# nm_main.net
KiCad netlist of a schematic drawn in Altium Designer
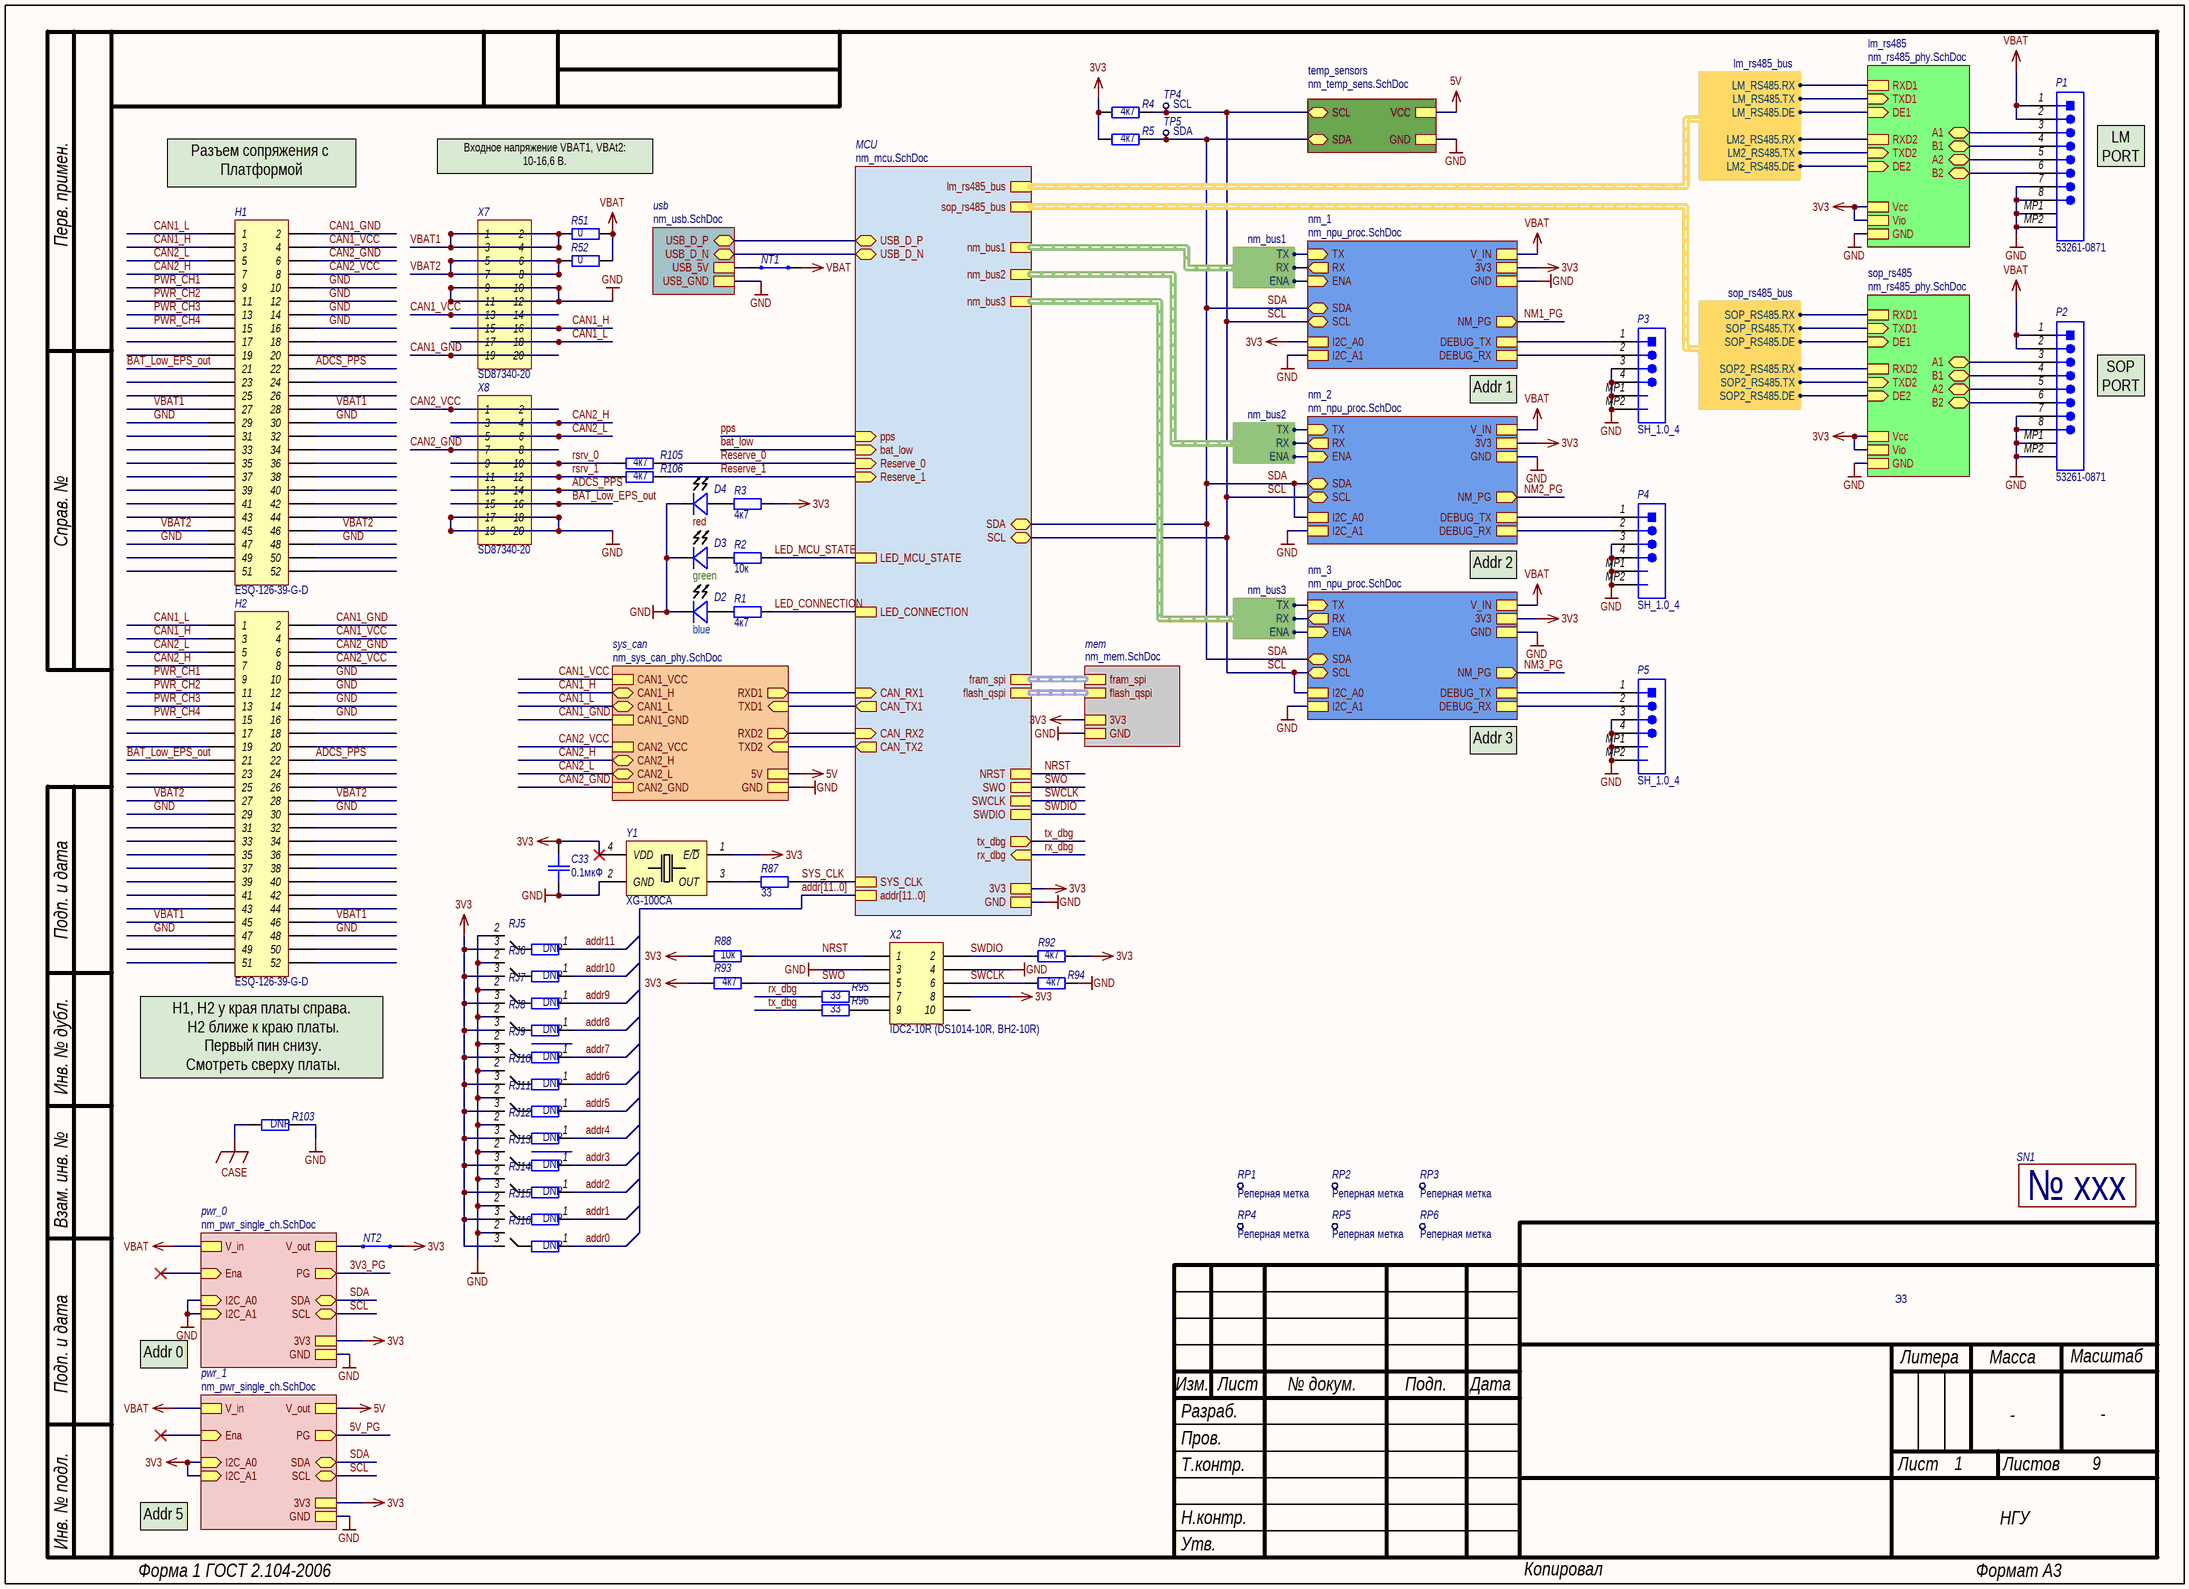
[diagram p0: nm_main.SchDoc]

(export (version "E")
  (design (tool "Eeschema 10.0.6"))
  (components
    (comp (ref "C33")
      (value "0.1мкФ")
      (footprint "SMD_C0603")
      (description "Capacitor")
      (libsource (lib "Passive") (part "Capacitor"))
    )
    (comp (ref "D2")
      (value "blue")
      (footprint "LED_0603")
      (fields (field (name "Comment") "LED"))
      (libsource (lib "LED") (part "LED"))
    )
    (comp (ref "D3")
      (value "green")
      (footprint "LED_0603")
      (fields (field (name "Comment") "LED"))
      (libsource (lib "LED") (part "LED"))
    )
    (comp (ref "D4")
      (value "red")
      (footprint "LED_0603")
      (fields (field (name "Comment") "LED"))
      (libsource (lib "LED") (part "LED"))
    )
    (comp (ref "H1")
      (value "ESQ-126-39-G-D")
      (footprint "ESQ-126-39-G-D")
      (description "Elevated socket, dual-row, 26-pin per row")
      (fields (field (name "НАИМЕНОВАНИЕ") "ESQ-126-39-G-D"))
      (libsource (lib "Connector") (part "ESQ-126-39-G-D"))
    )
    (comp (ref "H2")
      (value "ESQ-126-39-G-D")
      (footprint "ESQ-126-39-G-D")
      (description "Elevated socket, dual-row, 26-pin per row")
      (fields (field (name "НАИМЕНОВАНИЕ") "ESQ-126-39-G-D"))
      (libsource (lib "Connector") (part "ESQ-126-39-G-D"))
    )
    (comp (ref "NT1")
      (value "OSM R1-8")
      (footprint "NetTie_1mm")
      (description "Different Nets connection")
      (libsource (lib "Passive") (part "NetTie"))
    )
    (comp (ref "NT2")
      (value "OSM R1-8")
      (footprint "NetTie_1mm")
      (description "Different Nets connection")
      (libsource (lib "Passive") (part "NetTie"))
    )
    (comp (ref "P1")
      (value "53261-0871")
      (footprint "53261-0871")
      (description "Male Header, Pitch 1.25 mm, 1 x 8 Position, Height 3.4 mm, -40 to 85 degC, RoHS, Tape and Reel")
      (fields (field (name "НАИМЕНОВАНИЕ") "53261-0871"))
      (libsource (lib "Connector") (part "PicoBlade_53261-0871"))
    )
    (comp (ref "P2")
      (value "53261-0871")
      (footprint "53261-0871")
      (description "Male Header, Pitch 1.25 mm, 1 x 8 Position, Height 3.4 mm, -40 to 85 degC, RoHS, Tape and Reel")
      (fields (field (name "НАИМЕНОВАНИЕ") "53261-0871"))
      (libsource (lib "Connector") (part "PicoBlade_53261-0871"))
    )
    (comp (ref "P3")
      (value "SH_1.0_4")
      (footprint "53261-0471")
      (description "JST SH1.0, 1.0 mm pitch/Disconnactable crimp style connectors")
      (fields (field (name "НАИМЕНОВАНИЕ") "SH_1.0_4"))
      (libsource (lib "Connector") (part "SH_1.0_4"))
    )
    (comp (ref "P4")
      (value "SH_1.0_4")
      (footprint "53261-0471")
      (description "JST SH1.0, 1.0 mm pitch/Disconnactable crimp style connectors")
      (fields (field (name "НАИМЕНОВАНИЕ") "SH_1.0_4"))
      (libsource (lib "Connector") (part "SH_1.0_4"))
    )
    (comp (ref "P5")
      (value "SH_1.0_4")
      (footprint "53261-0471")
      (description "JST SH1.0, 1.0 mm pitch/Disconnactable crimp style connectors")
      (fields (field (name "НАИМЕНОВАНИЕ") "SH_1.0_4"))
      (libsource (lib "Connector") (part "SH_1.0_4"))
    )
    (comp (ref "R1")
      (value "4к7")
      (footprint "SMD_0603")
      (description "Resistor")
      (libsource (lib "") (part "Resistor_2"))
    )
    (comp (ref "R2")
      (value "10к")
      (footprint "SMD_0603")
      (description "Resistor")
      (libsource (lib "") (part "Resistor_2"))
    )
    (comp (ref "R3")
      (value "4к7")
      (footprint "SMD_0603")
      (description "Resistor")
      (libsource (lib "") (part "Resistor_2"))
    )
    (comp (ref "R4")
      (value "4к7")
      (footprint "SMD_0603")
      (description "Resistor")
      (libsource (lib "Passive") (part "Resistor"))
    )
    (comp (ref "R5")
      (value "4к7")
      (footprint "SMD_0603")
      (description "Resistor")
      (libsource (lib "Passive") (part "Resistor"))
    )
    (comp (ref "R51")
      (value "0")
      (footprint "SMD_1206")
      (description "Resistor")
      (libsource (lib "") (part "Resistor_3"))
    )
    (comp (ref "R52")
      (value "0")
      (footprint "SMD_1206")
      (description "Resistor")
      (libsource (lib "") (part "Resistor_3"))
    )
    (comp (ref "R87")
      (value "33")
      (footprint "SMD_0603")
      (description "Resistor")
      (libsource (lib "") (part "Resistor_1"))
    )
    (comp (ref "R88")
      (value "10к")
      (footprint "SMD_0603")
      (description "Resistor")
      (libsource (lib "") (part "Resistor_3"))
    )
    (comp (ref "R92")
      (value "4к7")
      (footprint "SMD_0603")
      (description "Resistor")
      (libsource (lib "") (part "Resistor_1"))
    )
    (comp (ref "R93")
      (value "4к7")
      (footprint "SMD_0603")
      (description "Resistor")
      (libsource (lib "Passive") (part "Resistor"))
    )
    (comp (ref "R94")
      (value "4к7")
      (footprint "SMD_0603")
      (description "Resistor")
      (libsource (lib "Passive") (part "Resistor"))
    )
    (comp (ref "R95")
      (value "33")
      (footprint "SMD_0603")
      (description "Resistor")
      (libsource (lib "") (part "Resistor_1"))
    )
    (comp (ref "R96")
      (value "33")
      (footprint "SMD_0603")
      (description "Resistor")
      (libsource (lib "") (part "Resistor_1"))
    )
    (comp (ref "R103")
      (value "DNP")
      (footprint "SMD_0805")
      (description "Resistor")
      (libsource (lib "Passive") (part "Resistor"))
    )
    (comp (ref "R105")
      (value "4к7")
      (footprint "SMD_0603")
      (description "Resistor")
      (libsource (lib "") (part "Resistor_2"))
    )
    (comp (ref "R106")
      (value "4к7")
      (footprint "SMD_0603")
      (description "Resistor")
      (libsource (lib "") (part "Resistor_2"))
    )
    (comp (ref "RJ5")
      (value "DNP")
      (footprint "SMD_JMP_0402")
      (description "Resistor-Jumper")
      (fields (field (name "Comment") "OSM R1-8"))
      (libsource (lib "Passive") (part "Resistor_Jamper"))
    )
    (comp (ref "RJ6")
      (value "DNP")
      (footprint "SMD_JMP_0402")
      (description "Resistor-Jumper")
      (fields (field (name "Comment") "OSM R1-8"))
      (libsource (lib "Passive") (part "Resistor_Jamper"))
    )
    (comp (ref "RJ7")
      (value "DNP")
      (footprint "SMD_JMP_0402")
      (description "Resistor-Jumper")
      (fields (field (name "Comment") "OSM R1-8"))
      (libsource (lib "Passive") (part "Resistor_Jamper"))
    )
    (comp (ref "RJ8")
      (value "DNP")
      (footprint "SMD_JMP_0402")
      (description "Resistor-Jumper")
      (fields (field (name "Comment") "OSM R1-8"))
      (libsource (lib "Passive") (part "Resistor_Jamper"))
    )
    (comp (ref "RJ9")
      (value "DNP")
      (footprint "SMD_JMP_0402")
      (description "Resistor-Jumper")
      (fields (field (name "Comment") "OSM R1-8"))
      (libsource (lib "Passive") (part "Resistor_Jamper"))
    )
    (comp (ref "RJ10")
      (value "DNP")
      (footprint "SMD_JMP_0402")
      (description "Resistor-Jumper")
      (fields (field (name "Comment") "OSM R1-8"))
      (libsource (lib "Passive") (part "Resistor_Jamper"))
    )
    (comp (ref "RJ11")
      (value "DNP")
      (footprint "SMD_JMP_0402")
      (description "Resistor-Jumper")
      (fields (field (name "Comment") "OSM R1-8"))
      (libsource (lib "Passive") (part "Resistor_Jamper"))
    )
    (comp (ref "RJ12")
      (value "DNP")
      (footprint "SMD_JMP_0402")
      (description "Resistor-Jumper")
      (fields (field (name "Comment") "OSM R1-8"))
      (libsource (lib "Passive") (part "Resistor_Jamper"))
    )
    (comp (ref "RJ13")
      (value "DNP")
      (footprint "SMD_JMP_0402")
      (description "Resistor-Jumper")
      (fields (field (name "Comment") "OSM R1-8"))
      (libsource (lib "Passive") (part "Resistor_Jamper"))
    )
    (comp (ref "RJ14")
      (value "DNP")
      (footprint "SMD_JMP_0402")
      (description "Resistor-Jumper")
      (fields (field (name "Comment") "OSM R1-8"))
      (libsource (lib "Passive") (part "Resistor_Jamper"))
    )
    (comp (ref "RJ15")
      (value "DNP")
      (footprint "SMD_JMP_0402")
      (description "Resistor-Jumper")
      (fields (field (name "Comment") "OSM R1-8"))
      (libsource (lib "Passive") (part "Resistor_Jamper"))
    )
    (comp (ref "RJ16")
      (value "DNP")
      (footprint "SMD_JMP_0402")
      (description "Resistor-Jumper")
      (fields (field (name "Comment") "OSM R1-8"))
      (libsource (lib "Passive") (part "Resistor_Jamper"))
    )
    (comp (ref "RP1")
      (value "RP")
      (footprint "ReperPoint")
      (fields (field (name "НАИМЕНОВАНИЕ") "Реперная метка"))
      (libsource (lib "Connector") (part "RP"))
    )
    (comp (ref "RP2")
      (value "RP")
      (footprint "ReperPoint")
      (fields (field (name "НАИМЕНОВАНИЕ") "Реперная метка"))
      (libsource (lib "Connector") (part "RP"))
    )
    (comp (ref "RP3")
      (value "RP")
      (footprint "ReperPoint")
      (fields (field (name "НАИМЕНОВАНИЕ") "Реперная метка"))
      (libsource (lib "Connector") (part "RP"))
    )
    (comp (ref "RP4")
      (value "RP")
      (footprint "ReperPoint")
      (fields (field (name "НАИМЕНОВАНИЕ") "Реперная метка"))
      (libsource (lib "Connector") (part "RP"))
    )
    (comp (ref "RP5")
      (value "RP")
      (footprint "ReperPoint")
      (fields (field (name "НАИМЕНОВАНИЕ") "Реперная метка"))
      (libsource (lib "Connector") (part "RP"))
    )
    (comp (ref "RP6")
      (value "RP")
      (footprint "ReperPoint")
      (fields (field (name "НАИМЕНОВАНИЕ") "Реперная метка"))
      (libsource (lib "Connector") (part "RP"))
    )
    (comp (ref "SN1")
      (value "Место под нанесение серийного номера")
      (footprint "Serial_number_v2")
      (libsource (lib "Serial_number") (part "Serial_number"))
    )
    (comp (ref "TP4")
      (value "SCL")
      (footprint "TP_PAD_1")
      (fields (field (name "TP_NAME") "SCL"))
      (libsource (lib "Connector") (part "TP"))
    )
    (comp (ref "TP5")
      (value "SDA")
      (footprint "TP_PAD_1")
      (fields (field (name "TP_NAME") "SDA"))
      (libsource (lib "Connector") (part "TP"))
    )
    (comp (ref "X2")
      (value "Header 2X10")
      (footprint "IDC2-10R")
      (description "Header, 10-Pin, Dual row")
      (fields (field (name "НАИМЕНОВАНИЕ") "IDC2-10R (DS1014-10R, BH2-10R)"))
      (libsource (lib "Header 2X10") (part "Header 2X10"))
    )
    (comp (ref "X7")
      (value "Header 2X20")
      (footprint "PLD2-20_SD87340-20")
      (description "Header, 20-Pin, Dual row")
      (fields (field (name "НАИМЕНОВАНИЕ") "SD87340-20"))
      (libsource (lib "Connector") (part "Header 2X20"))
    )
    (comp (ref "X8")
      (value "Header 2X20")
      (footprint "PLD2-20_SD87340-20")
      (description "Header, 20-Pin, Dual row")
      (fields (field (name "НАИМЕНОВАНИЕ") "SD87340-20"))
      (libsource (lib "Connector") (part "Header 2X20"))
    )
    (comp (ref "Y1")
      (value "XG-1000CA")
      (footprint "SMD_7050_Crystal_Oscillator")
      (description "Crystall oscillator, CMOS, 3.3V, SMD7050")
      (fields (field (name "НАИМЕНОВАНИЕ") "XG-100CA"))
      (libsource (lib "Oscillator") (part "Crystal_Oscillator"))
    )
  )
  (nets
    (net (code "8") (name "/A1") (class "Default")
      (node (ref "P1") (pin "3") (pinfunction "3_3") (pintype "passive"))
    )
    (net (code "9") (name "/A1_1") (class "Default")
      (node (ref "P2") (pin "3") (pinfunction "3_3") (pintype "passive"))
    )
    (net (code "10") (name "/A2") (class "Default")
      (node (ref "P1") (pin "5") (pinfunction "5_5") (pintype "passive"))
    )
    (net (code "11") (name "/A2_1") (class "Default")
      (node (ref "P2") (pin "5") (pinfunction "5_5") (pintype "passive"))
    )
    (net (code "12") (name "/ADCS_PPS") (class "Default")
      (node (ref "H1") (pin "22") (pinfunction "22_22") (pintype "passive"))
      (node (ref "H2") (pin "22") (pinfunction "22_22") (pintype "passive"))
      (node (ref "X8") (pin "13") (pinfunction "13_13") (pintype "passive"))
      (node (ref "X8") (pin "14") (pinfunction "14_14") (pintype "passive"))
    )
    (net (code "13") (name "/B1") (class "Default")
      (node (ref "P1") (pin "4") (pinfunction "4_4") (pintype "passive"))
    )
    (net (code "14") (name "/B1_1") (class "Default")
      (node (ref "P2") (pin "4") (pinfunction "4_4") (pintype "passive"))
    )
    (net (code "15") (name "/B2") (class "Default")
      (node (ref "P1") (pin "6") (pinfunction "6_6") (pintype "passive"))
    )
    (net (code "16") (name "/B2_1") (class "Default")
      (node (ref "P2") (pin "6") (pinfunction "6_6") (pintype "passive"))
    )
    (net (code "17") (name "/BAT_Low_EPS_out") (class "Default")
      (node (ref "H1") (pin "21") (pinfunction "21_21") (pintype "passive"))
      (node (ref "H2") (pin "21") (pinfunction "21_21") (pintype "passive"))
      (node (ref "X8") (pin "15") (pinfunction "15_15") (pintype "passive"))
      (node (ref "X8") (pin "16") (pinfunction "16_16") (pintype "passive"))
    )
    (net (code "18") (name "/CAN1_GND") (class "Default")
      (node (ref "H1") (pin "2") (pinfunction "2_2") (pintype "passive"))
      (node (ref "H2") (pin "2") (pinfunction "2_2") (pintype "passive"))
      (node (ref "X7") (pin "19") (pinfunction "19_19") (pintype "passive"))
      (node (ref "X7") (pin "20") (pinfunction "20_20") (pintype "passive"))
    )
    (net (code "19") (name "/CAN1_H") (class "Default")
      (node (ref "H1") (pin "3") (pinfunction "3_3") (pintype "passive"))
      (node (ref "H2") (pin "3") (pinfunction "3_3") (pintype "passive"))
      (node (ref "X7") (pin "15") (pinfunction "15_15") (pintype "passive"))
      (node (ref "X7") (pin "16") (pinfunction "16_16") (pintype "passive"))
    )
    (net (code "20") (name "/CAN1_L") (class "Default")
      (node (ref "H1") (pin "1") (pinfunction "1_1") (pintype "passive"))
      (node (ref "H2") (pin "1") (pinfunction "1_1") (pintype "passive"))
      (node (ref "X7") (pin "17") (pinfunction "17_17") (pintype "passive"))
      (node (ref "X7") (pin "18") (pinfunction "18_18") (pintype "passive"))
    )
    (net (code "21") (name "/CAN1_VCC") (class "Default")
      (node (ref "H1") (pin "4") (pinfunction "4_4") (pintype "passive"))
      (node (ref "H2") (pin "4") (pinfunction "4_4") (pintype "passive"))
      (node (ref "X7") (pin "13") (pinfunction "13_13") (pintype "passive"))
      (node (ref "X7") (pin "14") (pinfunction "14_14") (pintype "passive"))
    )
    (net (code "22") (name "/CAN2_GND") (class "Default")
      (node (ref "H1") (pin "6") (pinfunction "6_6") (pintype "passive"))
      (node (ref "H2") (pin "6") (pinfunction "6_6") (pintype "passive"))
      (node (ref "X8") (pin "7") (pinfunction "7_7") (pintype "passive"))
      (node (ref "X8") (pin "8") (pinfunction "8_8") (pintype "passive"))
    )
    (net (code "23") (name "/CAN2_H") (class "Default")
      (node (ref "H1") (pin "7") (pinfunction "7_7") (pintype "passive"))
      (node (ref "H2") (pin "7") (pinfunction "7_7") (pintype "passive"))
      (node (ref "X8") (pin "3") (pinfunction "3_3") (pintype "passive"))
      (node (ref "X8") (pin "4") (pinfunction "4_4") (pintype "passive"))
    )
    (net (code "24") (name "/CAN2_L") (class "Default")
      (node (ref "H1") (pin "5") (pinfunction "5_5") (pintype "passive"))
      (node (ref "H2") (pin "5") (pinfunction "5_5") (pintype "passive"))
      (node (ref "X8") (pin "5") (pinfunction "5_5") (pintype "passive"))
      (node (ref "X8") (pin "6") (pinfunction "6_6") (pintype "passive"))
    )
    (net (code "25") (name "/CAN2_VCC") (class "Default")
      (node (ref "H1") (pin "8") (pinfunction "8_8") (pintype "passive"))
      (node (ref "H2") (pin "8") (pinfunction "8_8") (pintype "passive"))
      (node (ref "X8") (pin "1") (pinfunction "1_1") (pintype "passive"))
      (node (ref "X8") (pin "2") (pinfunction "2_2") (pintype "passive"))
    )
    (net (code "32") (name "/DEBUG_RX") (class "Default")
      (node (ref "P3") (pin "2") (pinfunction "2_2") (pintype "passive"))
    )
    (net (code "33") (name "/DEBUG_RX_1") (class "Default")
      (node (ref "P4") (pin "2") (pinfunction "2_2") (pintype "passive"))
    )
    (net (code "34") (name "/DEBUG_RX_2") (class "Default")
      (node (ref "P5") (pin "2") (pinfunction "2_2") (pintype "passive"))
    )
    (net (code "35") (name "/DEBUG_TX") (class "Default")
      (node (ref "P3") (pin "1") (pinfunction "1_1") (pintype "passive"))
    )
    (net (code "36") (name "/DEBUG_TX_1") (class "Default")
      (node (ref "P4") (pin "1") (pinfunction "1_1") (pintype "passive"))
    )
    (net (code "37") (name "/DEBUG_TX_2") (class "Default")
      (node (ref "P5") (pin "1") (pinfunction "1_1") (pintype "passive"))
    )
    (net (code "43") (name "/LED_CONNECTION") (class "Default")
      (node (ref "R1") (pin "1") (pinfunction "1_1") (pintype "passive"))
    )
    (net (code "44") (name "/LED_MCU_STATE") (class "Default")
      (node (ref "R2") (pin "1") (pinfunction "1_1") (pintype "passive"))
    )
    (net (code "48") (name "/NRST") (class "Default")
      (node (ref "R88") (pin "2") (pinfunction "2_2") (pintype "passive"))
      (node (ref "X2") (pin "1") (pinfunction "1_1") (pintype "passive"))
    )
    (net (code "49") (name "/PWR_CH1") (class "Default")
      (node (ref "H1") (pin "9") (pinfunction "9_9") (pintype "passive"))
      (node (ref "H2") (pin "9") (pinfunction "9_9") (pintype "passive"))
    )
    (net (code "50") (name "/PWR_CH2") (class "Default")
      (node (ref "H1") (pin "11") (pinfunction "11_11") (pintype "passive"))
      (node (ref "H2") (pin "11") (pinfunction "11_11") (pintype "passive"))
    )
    (net (code "51") (name "/PWR_CH3") (class "Default")
      (node (ref "H1") (pin "13") (pinfunction "13_13") (pintype "passive"))
      (node (ref "H2") (pin "13") (pinfunction "13_13") (pintype "passive"))
    )
    (net (code "52") (name "/PWR_CH4") (class "Default")
      (node (ref "H1") (pin "15") (pinfunction "15_15") (pintype "passive"))
      (node (ref "H2") (pin "15") (pinfunction "15_15") (pintype "passive"))
    )
    (net (code "62") (name "/Reserve_0") (class "Default")
      (node (ref "R105") (pin "1") (pinfunction "1_1") (pintype "passive"))
    )
    (net (code "63") (name "/Reserve_1") (class "Default")
      (node (ref "R106") (pin "1") (pinfunction "1_1") (pintype "passive"))
    )
    (net (code "64") (name "/SCL") (class "Default")
      (node (ref "R4") (pin "1") (pinfunction "1_1") (pintype "passive"))
      (node (ref "TP4") (pin "0") (pinfunction "TP_0") (pintype "passive"))
    )
    (net (code "65") (name "/SDA") (class "Default")
      (node (ref "R5") (pin "1") (pinfunction "1_1") (pintype "passive"))
      (node (ref "TP5") (pin "0") (pinfunction "TP_0") (pintype "passive"))
    )
    (net (code "66") (name "/SWCLK") (class "Default")
      (node (ref "R94") (pin "2") (pinfunction "2_2") (pintype "passive"))
      (node (ref "X2") (pin "6") (pinfunction "6_6") (pintype "passive"))
    )
    (net (code "67") (name "/SWDIO") (class "Default")
      (node (ref "R92") (pin "1") (pinfunction "1_1") (pintype "passive"))
      (node (ref "X2") (pin "2") (pinfunction "2_2") (pintype "passive"))
    )
    (net (code "68") (name "/SWO") (class "Default")
      (node (ref "R93") (pin "1") (pinfunction "1_1") (pintype "passive"))
      (node (ref "X2") (pin "5") (pinfunction "5_5") (pintype "passive"))
    )
    (net (code "69") (name "/SYS_CLK") (class "Default")
      (node (ref "R87") (pin "2") (pinfunction "2_2") (pintype "passive"))
    )
    (net (code "77") (name "/USB_5V") (class "Default")
      (node (ref "NT1") (pin "1") (pinfunction "1_1") (pintype "passive"))
    )
    (net (code "80") (name "/VBAT1") (class "Default")
      (node (ref "H1") (pin "27") (pinfunction "27_27") (pintype "passive"))
      (node (ref "H1") (pin "28") (pinfunction "28_28") (pintype "passive"))
      (node (ref "H2") (pin "45") (pinfunction "45_45") (pintype "passive"))
      (node (ref "H2") (pin "46") (pinfunction "46_46") (pintype "passive"))
      (node (ref "R51") (pin "1") (pinfunction "1_1") (pintype "passive"))
      (node (ref "X7") (pin "1") (pinfunction "1_1") (pintype "passive"))
      (node (ref "X7") (pin "2") (pinfunction "2_2") (pintype "passive"))
      (node (ref "X7") (pin "3") (pinfunction "3_3") (pintype "passive"))
      (node (ref "X7") (pin "4") (pinfunction "4_4") (pintype "passive"))
    )
    (net (code "81") (name "/VBAT2") (class "Default")
      (node (ref "H1") (pin "45") (pinfunction "45_45") (pintype "passive"))
      (node (ref "H1") (pin "46") (pinfunction "46_46") (pintype "passive"))
      (node (ref "H2") (pin "27") (pinfunction "27_27") (pintype "passive"))
      (node (ref "H2") (pin "28") (pinfunction "28_28") (pintype "passive"))
      (node (ref "R52") (pin "1") (pinfunction "1_1") (pintype "passive"))
      (node (ref "X7") (pin "5") (pinfunction "5_5") (pintype "passive"))
      (node (ref "X7") (pin "6") (pinfunction "6_6") (pintype "passive"))
      (node (ref "X7") (pin "7") (pinfunction "7_7") (pintype "passive"))
      (node (ref "X7") (pin "8") (pinfunction "8_8") (pintype "passive"))
    )
    (net (code "82") (name "/V_out") (class "Default")
      (node (ref "NT2") (pin "1") (pinfunction "1_1") (pintype "passive"))
    )
    (net (code "83") (name "/addr0") (class "Default") (node (ref "RJ16") (pin "1") (pintype "passive")))
    (net (code "84") (name "/addr1") (class "Default") (node (ref "RJ15") (pin "1") (pintype "passive")))
    (net (code "85") (name "/addr2") (class "Default") (node (ref "RJ14") (pin "1") (pintype "passive")))
    (net (code "86") (name "/addr3") (class "Default") (node (ref "RJ13") (pin "1") (pintype "passive")))
    (net (code "87") (name "/addr4") (class "Default") (node (ref "RJ12") (pin "1") (pintype "passive")))
    (net (code "88") (name "/addr5") (class "Default") (node (ref "RJ11") (pin "1") (pintype "passive")))
    (net (code "89") (name "/addr6") (class "Default") (node (ref "RJ10") (pin "1") (pintype "passive")))
    (net (code "90") (name "/addr7") (class "Default") (node (ref "RJ9") (pin "1") (pintype "passive")))
    (net (code "91") (name "/addr8") (class "Default") (node (ref "RJ8") (pin "1") (pintype "passive")))
    (net (code "92") (name "/addr9") (class "Default") (node (ref "RJ7") (pin "1") (pintype "passive")))
    (net (code "93") (name "/addr10") (class "Default") (node (ref "RJ6") (pin "1") (pintype "passive")))
    (net (code "94") (name "/addr11") (class "Default") (node (ref "RJ5") (pin "1") (pintype "passive")))
    (net (code "100") (name "/rsrv_0") (class "Default")
      (node (ref "R105") (pin "2") (pinfunction "2_2") (pintype "passive"))
      (node (ref "X8") (pin "10") (pinfunction "10_10") (pintype "passive"))
      (node (ref "X8") (pin "9") (pinfunction "9_9") (pintype "passive"))
    )
    (net (code "101") (name "/rsrv_1") (class "Default")
      (node (ref "R106") (pin "2") (pinfunction "2_2") (pintype "passive"))
      (node (ref "X8") (pin "11") (pinfunction "11_11") (pintype "passive"))
      (node (ref "X8") (pin "12") (pinfunction "12_12") (pintype "passive"))
    )
    (net (code "102") (name "/rx_dbg") (class "Default")
      (node (ref "R95") (pin "1") (pinfunction "1_1") (pintype "passive"))
    )
    (net (code "103") (name "/tx_dbg") (class "Default")
      (node (ref "R96") (pin "1") (pinfunction "1_1") (pintype "passive"))
    )
    (net (code "109") (name "3V3") (class "Default")
      (node (ref "C33") (pin "2") (pinfunction "2_2") (pintype "passive"))
      (node (ref "NT2") (pin "2") (pinfunction "2_2") (pintype "passive"))
      (node (ref "R3") (pin "1") (pinfunction "1_1") (pintype "passive"))
      (node (ref "R4") (pin "2") (pinfunction "2_2") (pintype "passive"))
      (node (ref "R5") (pin "2") (pinfunction "2_2") (pintype "passive"))
      (node (ref "R88") (pin "1") (pinfunction "1_1") (pintype "passive"))
      (node (ref "R92") (pin "2") (pinfunction "2_2") (pintype "passive"))
      (node (ref "R93") (pin "2") (pinfunction "2_2") (pintype "passive"))
      (node (ref "RJ10") (pin "3") (pintype "passive"))
      (node (ref "RJ11") (pin "3") (pintype "passive"))
      (node (ref "RJ12") (pin "3") (pintype "passive"))
      (node (ref "RJ13") (pin "3") (pintype "passive"))
      (node (ref "RJ14") (pin "3") (pintype "passive"))
      (node (ref "RJ15") (pin "3") (pintype "passive"))
      (node (ref "RJ16") (pin "3") (pintype "passive"))
      (node (ref "RJ5") (pin "3") (pintype "passive"))
      (node (ref "RJ6") (pin "3") (pintype "passive"))
      (node (ref "RJ7") (pin "3") (pintype "passive"))
      (node (ref "RJ8") (pin "3") (pintype "passive"))
      (node (ref "RJ9") (pin "3") (pintype "passive"))
      (node (ref "X2") (pin "8") (pinfunction "8_8") (pintype "passive"))
      (node (ref "Y1") (pin "1") (pinfunction "E/~{D}_1") (pintype "passive"))
      (node (ref "Y1") (pin "4") (pinfunction "VDD_4") (pintype "passive"))
    )
    (net (code "111") (name "CASE") (class "Default")
      (node (ref "R103") (pin "2") (pinfunction "2_2") (pintype "passive"))
    )
    (net (code "112") (name "GND") (class "Default")
      (node (ref "C33") (pin "1") (pinfunction "1_1") (pintype "passive"))
      (node (ref "D2") (pin "2") (pinfunction "K_2") (pintype "passive"))
      (node (ref "D3") (pin "2") (pinfunction "K_2") (pintype "passive"))
      (node (ref "D4") (pin "2") (pinfunction "K_2") (pintype "passive"))
      (node (ref "H1") (pin "10") (pinfunction "10_10") (pintype "passive"))
      (node (ref "H1") (pin "12") (pinfunction "12_12") (pintype "passive"))
      (node (ref "H1") (pin "14") (pinfunction "14_14") (pintype "passive"))
      (node (ref "H1") (pin "16") (pinfunction "16_16") (pintype "passive"))
      (node (ref "H1") (pin "29") (pinfunction "29_29") (pintype "passive"))
      (node (ref "H1") (pin "30") (pinfunction "30_30") (pintype "passive"))
      (node (ref "H1") (pin "47") (pinfunction "47_47") (pintype "passive"))
      (node (ref "H1") (pin "48") (pinfunction "48_48") (pintype "passive"))
      (node (ref "H2") (pin "10") (pinfunction "10_10") (pintype "passive"))
      (node (ref "H2") (pin "12") (pinfunction "12_12") (pintype "passive"))
      (node (ref "H2") (pin "14") (pinfunction "14_14") (pintype "passive"))
      (node (ref "H2") (pin "16") (pinfunction "16_16") (pintype "passive"))
      (node (ref "H2") (pin "29") (pinfunction "29_29") (pintype "passive"))
      (node (ref "H2") (pin "30") (pinfunction "30_30") (pintype "passive"))
      (node (ref "H2") (pin "47") (pinfunction "47_47") (pintype "passive"))
      (node (ref "H2") (pin "48") (pinfunction "48_48") (pintype "passive"))
      (node (ref "P1") (pin "7") (pinfunction "7_7") (pintype "passive"))
      (node (ref "P1") (pin "8") (pinfunction "8_8") (pintype "passive"))
      (node (ref "P1") (pin "MP1") (pinfunction "MP1_MP1") (pintype "passive"))
      (node (ref "P1") (pin "MP2") (pinfunction "MP2_MP2") (pintype "passive"))
      (node (ref "P2") (pin "7") (pinfunction "7_7") (pintype "passive"))
      (node (ref "P2") (pin "8") (pinfunction "8_8") (pintype "passive"))
      (node (ref "P2") (pin "MP1") (pinfunction "MP1_MP1") (pintype "passive"))
      (node (ref "P2") (pin "MP2") (pinfunction "MP2_MP2") (pintype "passive"))
      (node (ref "P3") (pin "3") (pinfunction "3_3") (pintype "passive"))
      (node (ref "P3") (pin "4") (pinfunction "4_4") (pintype "passive"))
      (node (ref "P3") (pin "MP1") (pinfunction "MP1_MP1") (pintype "passive"))
      (node (ref "P3") (pin "MP2") (pinfunction "MP2_MP2") (pintype "passive"))
      (node (ref "P4") (pin "3") (pinfunction "3_3") (pintype "passive"))
      (node (ref "P4") (pin "4") (pinfunction "4_4") (pintype "passive"))
      (node (ref "P4") (pin "MP1") (pinfunction "MP1_MP1") (pintype "passive"))
      (node (ref "P4") (pin "MP2") (pinfunction "MP2_MP2") (pintype "passive"))
      (node (ref "P5") (pin "3") (pinfunction "3_3") (pintype "passive"))
      (node (ref "P5") (pin "4") (pinfunction "4_4") (pintype "passive"))
      (node (ref "P5") (pin "MP1") (pinfunction "MP1_MP1") (pintype "passive"))
      (node (ref "P5") (pin "MP2") (pinfunction "MP2_MP2") (pintype "passive"))
      (node (ref "R103") (pin "1") (pinfunction "1_1") (pintype "passive"))
      (node (ref "R94") (pin "1") (pinfunction "1_1") (pintype "passive"))
      (node (ref "RJ10") (pin "2") (pintype "passive"))
      (node (ref "RJ11") (pin "2") (pintype "passive"))
      (node (ref "RJ12") (pin "2") (pintype "passive"))
      (node (ref "RJ13") (pin "2") (pintype "passive"))
      (node (ref "RJ14") (pin "2") (pintype "passive"))
      (node (ref "RJ15") (pin "2") (pintype "passive"))
      (node (ref "RJ16") (pin "2") (pintype "passive"))
      (node (ref "RJ5") (pin "2") (pintype "passive"))
      (node (ref "RJ6") (pin "2") (pintype "passive"))
      (node (ref "RJ7") (pin "2") (pintype "passive"))
      (node (ref "RJ8") (pin "2") (pintype "passive"))
      (node (ref "RJ9") (pin "2") (pintype "passive"))
      (node (ref "X2") (pin "3") (pinfunction "3_3") (pintype "passive"))
      (node (ref "X2") (pin "4") (pinfunction "4_4") (pintype "passive"))
      (node (ref "X7") (pin "10") (pinfunction "10_10") (pintype "passive"))
      (node (ref "X7") (pin "11") (pinfunction "11_11") (pintype "passive"))
      (node (ref "X7") (pin "12") (pinfunction "12_12") (pintype "passive"))
      (node (ref "X7") (pin "9") (pinfunction "9_9") (pintype "passive"))
      (node (ref "X8") (pin "17") (pinfunction "17_17") (pintype "passive"))
      (node (ref "X8") (pin "18") (pinfunction "18_18") (pintype "passive"))
      (node (ref "X8") (pin "19") (pinfunction "19_19") (pintype "passive"))
      (node (ref "X8") (pin "20") (pinfunction "20_20") (pintype "passive"))
      (node (ref "Y1") (pin "2") (pinfunction "GND_2") (pintype "passive"))
    )
    (net (code "113") (name "Net-(D2-A)") (class "Default")
      (node (ref "D2") (pin "1") (pinfunction "A_1") (pintype "passive"))
      (node (ref "R1") (pin "2") (pinfunction "2_2") (pintype "passive"))
    )
    (net (code "114") (name "Net-(D3-A)") (class "Default")
      (node (ref "D3") (pin "1") (pinfunction "A_1") (pintype "passive"))
      (node (ref "R2") (pin "2") (pinfunction "2_2") (pintype "passive"))
    )
    (net (code "115") (name "Net-(D4-A)") (class "Default")
      (node (ref "D4") (pin "1") (pinfunction "A_1") (pintype "passive"))
      (node (ref "R3") (pin "2") (pinfunction "2_2") (pintype "passive"))
    )
    (net (code "116") (name "Net-(R95-Pad2)") (class "Default")
      (node (ref "R95") (pin "2") (pinfunction "2_2") (pintype "passive"))
      (node (ref "X2") (pin "7") (pinfunction "7_7") (pintype "passive"))
    )
    (net (code "117") (name "Net-(R96-Pad2)") (class "Default")
      (node (ref "R96") (pin "2") (pinfunction "2_2") (pintype "passive"))
      (node (ref "X2") (pin "9") (pinfunction "9_9") (pintype "passive"))
    )
    (net (code "118") (name "Net-(Y1-OUT)") (class "Default")
      (node (ref "R87") (pin "1") (pinfunction "1_1") (pintype "passive"))
      (node (ref "Y1") (pin "3") (pinfunction "OUT_3") (pintype "passive"))
    )
    (net (code "119") (name "VBAT") (class "Default")
      (node (ref "NT1") (pin "2") (pinfunction "2_2") (pintype "passive"))
      (node (ref "P1") (pin "1") (pinfunction "1_1") (pintype "passive"))
      (node (ref "P1") (pin "2") (pinfunction "2_2") (pintype "passive"))
      (node (ref "P2") (pin "1") (pinfunction "1_1") (pintype "passive"))
      (node (ref "P2") (pin "2") (pinfunction "2_2") (pintype "passive"))
      (node (ref "R51") (pin "2") (pinfunction "2_2") (pintype "passive"))
      (node (ref "R52") (pin "2") (pinfunction "2_2") (pintype "passive"))
    )
    (net (code "120") (name "unconnected-(H1-Pad17)") (class "Default")
      (node (ref "H1") (pin "17") (pinfunction "17_17") (pintype "passive"))
    )
    (net (code "121") (name "unconnected-(H1-Pad18)") (class "Default")
      (node (ref "H1") (pin "18") (pinfunction "18_18") (pintype "passive"))
    )
    (net (code "122") (name "unconnected-(H1-Pad19)") (class "Default")
      (node (ref "H1") (pin "19") (pinfunction "19_19") (pintype "passive"))
    )
    (net (code "123") (name "unconnected-(H1-Pad20)") (class "Default")
      (node (ref "H1") (pin "20") (pinfunction "20_20") (pintype "passive"))
    )
    (net (code "124") (name "unconnected-(H1-Pad23)") (class "Default")
      (node (ref "H1") (pin "23") (pinfunction "23_23") (pintype "passive"))
    )
    (net (code "125") (name "unconnected-(H1-Pad24)") (class "Default")
      (node (ref "H1") (pin "24") (pinfunction "24_24") (pintype "passive"))
    )
    (net (code "126") (name "unconnected-(H1-Pad25)") (class "Default")
      (node (ref "H1") (pin "25") (pinfunction "25_25") (pintype "passive"))
    )
    (net (code "127") (name "unconnected-(H1-Pad26)") (class "Default")
      (node (ref "H1") (pin "26") (pinfunction "26_26") (pintype "passive"))
    )
    (net (code "128") (name "unconnected-(H1-Pad31)") (class "Default")
      (node (ref "H1") (pin "31") (pinfunction "31_31") (pintype "passive"))
    )
    (net (code "129") (name "unconnected-(H1-Pad32)") (class "Default")
      (node (ref "H1") (pin "32") (pinfunction "32_32") (pintype "passive"))
    )
    (net (code "130") (name "unconnected-(H1-Pad33)") (class "Default")
      (node (ref "H1") (pin "33") (pinfunction "33_33") (pintype "passive"))
    )
    (net (code "131") (name "unconnected-(H1-Pad34)") (class "Default")
      (node (ref "H1") (pin "34") (pinfunction "34_34") (pintype "passive"))
    )
    (net (code "132") (name "unconnected-(H1-Pad35)") (class "Default")
      (node (ref "H1") (pin "35") (pinfunction "35_35") (pintype "passive"))
    )
    (net (code "133") (name "unconnected-(H1-Pad36)") (class "Default")
      (node (ref "H1") (pin "36") (pinfunction "36_36") (pintype "passive"))
    )
    (net (code "134") (name "unconnected-(H1-Pad37)") (class "Default")
      (node (ref "H1") (pin "37") (pinfunction "37_37") (pintype "passive"))
    )
    (net (code "135") (name "unconnected-(H1-Pad38)") (class "Default")
      (node (ref "H1") (pin "38") (pinfunction "38_38") (pintype "passive"))
    )
    (net (code "136") (name "unconnected-(H1-Pad39)") (class "Default")
      (node (ref "H1") (pin "39") (pinfunction "39_39") (pintype "passive"))
    )
    (net (code "137") (name "unconnected-(H1-Pad40)") (class "Default")
      (node (ref "H1") (pin "40") (pinfunction "40_40") (pintype "passive"))
    )
    (net (code "138") (name "unconnected-(H1-Pad41)") (class "Default")
      (node (ref "H1") (pin "41") (pinfunction "41_41") (pintype "passive"))
    )
    (net (code "139") (name "unconnected-(H1-Pad42)") (class "Default")
      (node (ref "H1") (pin "42") (pinfunction "42_42") (pintype "passive"))
    )
    (net (code "140") (name "unconnected-(H1-Pad43)") (class "Default")
      (node (ref "H1") (pin "43") (pinfunction "43_43") (pintype "passive"))
    )
    (net (code "141") (name "unconnected-(H1-Pad44)") (class "Default")
      (node (ref "H1") (pin "44") (pinfunction "44_44") (pintype "passive"))
    )
    (net (code "142") (name "unconnected-(H1-Pad49)") (class "Default")
      (node (ref "H1") (pin "49") (pinfunction "49_49") (pintype "passive"))
    )
    (net (code "143") (name "unconnected-(H1-Pad50)") (class "Default")
      (node (ref "H1") (pin "50") (pinfunction "50_50") (pintype "passive"))
    )
    (net (code "144") (name "unconnected-(H1-Pad51)") (class "Default")
      (node (ref "H1") (pin "51") (pinfunction "51_51") (pintype "passive"))
    )
    (net (code "145") (name "unconnected-(H1-Pad52)") (class "Default")
      (node (ref "H1") (pin "52") (pinfunction "52_52") (pintype "passive"))
    )
    (net (code "146") (name "unconnected-(H2-Pad17)") (class "Default")
      (node (ref "H2") (pin "17") (pinfunction "17_17") (pintype "passive"))
    )
    (net (code "147") (name "unconnected-(H2-Pad18)") (class "Default")
      (node (ref "H2") (pin "18") (pinfunction "18_18") (pintype "passive"))
    )
    (net (code "148") (name "unconnected-(H2-Pad19)") (class "Default")
      (node (ref "H2") (pin "19") (pinfunction "19_19") (pintype "passive"))
    )
    (net (code "149") (name "unconnected-(H2-Pad20)") (class "Default")
      (node (ref "H2") (pin "20") (pinfunction "20_20") (pintype "passive"))
    )
    (net (code "150") (name "unconnected-(H2-Pad23)") (class "Default")
      (node (ref "H2") (pin "23") (pinfunction "23_23") (pintype "passive"))
    )
    (net (code "151") (name "unconnected-(H2-Pad24)") (class "Default")
      (node (ref "H2") (pin "24") (pinfunction "24_24") (pintype "passive"))
    )
    (net (code "152") (name "unconnected-(H2-Pad25)") (class "Default")
      (node (ref "H2") (pin "25") (pinfunction "25_25") (pintype "passive"))
    )
    (net (code "153") (name "unconnected-(H2-Pad26)") (class "Default")
      (node (ref "H2") (pin "26") (pinfunction "26_26") (pintype "passive"))
    )
    (net (code "154") (name "unconnected-(H2-Pad31)") (class "Default")
      (node (ref "H2") (pin "31") (pinfunction "31_31") (pintype "passive"))
    )
    (net (code "155") (name "unconnected-(H2-Pad32)") (class "Default")
      (node (ref "H2") (pin "32") (pinfunction "32_32") (pintype "passive"))
    )
    (net (code "156") (name "unconnected-(H2-Pad33)") (class "Default")
      (node (ref "H2") (pin "33") (pinfunction "33_33") (pintype "passive"))
    )
    (net (code "157") (name "unconnected-(H2-Pad34)") (class "Default")
      (node (ref "H2") (pin "34") (pinfunction "34_34") (pintype "passive"))
    )
    (net (code "158") (name "unconnected-(H2-Pad35)") (class "Default")
      (node (ref "H2") (pin "35") (pinfunction "35_35") (pintype "passive"))
    )
    (net (code "159") (name "unconnected-(H2-Pad36)") (class "Default")
      (node (ref "H2") (pin "36") (pinfunction "36_36") (pintype "passive"))
    )
    (net (code "160") (name "unconnected-(H2-Pad37)") (class "Default")
      (node (ref "H2") (pin "37") (pinfunction "37_37") (pintype "passive"))
    )
    (net (code "161") (name "unconnected-(H2-Pad38)") (class "Default")
      (node (ref "H2") (pin "38") (pinfunction "38_38") (pintype "passive"))
    )
    (net (code "162") (name "unconnected-(H2-Pad39)") (class "Default")
      (node (ref "H2") (pin "39") (pinfunction "39_39") (pintype "passive"))
    )
    (net (code "163") (name "unconnected-(H2-Pad40)") (class "Default")
      (node (ref "H2") (pin "40") (pinfunction "40_40") (pintype "passive"))
    )
    (net (code "164") (name "unconnected-(H2-Pad41)") (class "Default")
      (node (ref "H2") (pin "41") (pinfunction "41_41") (pintype "passive"))
    )
    (net (code "165") (name "unconnected-(H2-Pad42)") (class "Default")
      (node (ref "H2") (pin "42") (pinfunction "42_42") (pintype "passive"))
    )
    (net (code "166") (name "unconnected-(H2-Pad43)") (class "Default")
      (node (ref "H2") (pin "43") (pinfunction "43_43") (pintype "passive"))
    )
    (net (code "167") (name "unconnected-(H2-Pad44)") (class "Default")
      (node (ref "H2") (pin "44") (pinfunction "44_44") (pintype "passive"))
    )
    (net (code "168") (name "unconnected-(H2-Pad49)") (class "Default")
      (node (ref "H2") (pin "49") (pinfunction "49_49") (pintype "passive"))
    )
    (net (code "169") (name "unconnected-(H2-Pad50)") (class "Default")
      (node (ref "H2") (pin "50") (pinfunction "50_50") (pintype "passive"))
    )
    (net (code "170") (name "unconnected-(H2-Pad51)") (class "Default")
      (node (ref "H2") (pin "51") (pinfunction "51_51") (pintype "passive"))
    )
    (net (code "171") (name "unconnected-(H2-Pad52)") (class "Default")
      (node (ref "H2") (pin "52") (pinfunction "52_52") (pintype "passive"))
    )
    (net (code "172") (name "unconnected-(X2-Pad10)") (class "Default")
      (node (ref "X2") (pin "10") (pinfunction "10_10") (pintype "passive"))
    )
  )
)
